# SCH_E-nose-Design_2025-10-13.net
KiCad netlist of a schematic drawn in EasyEDA
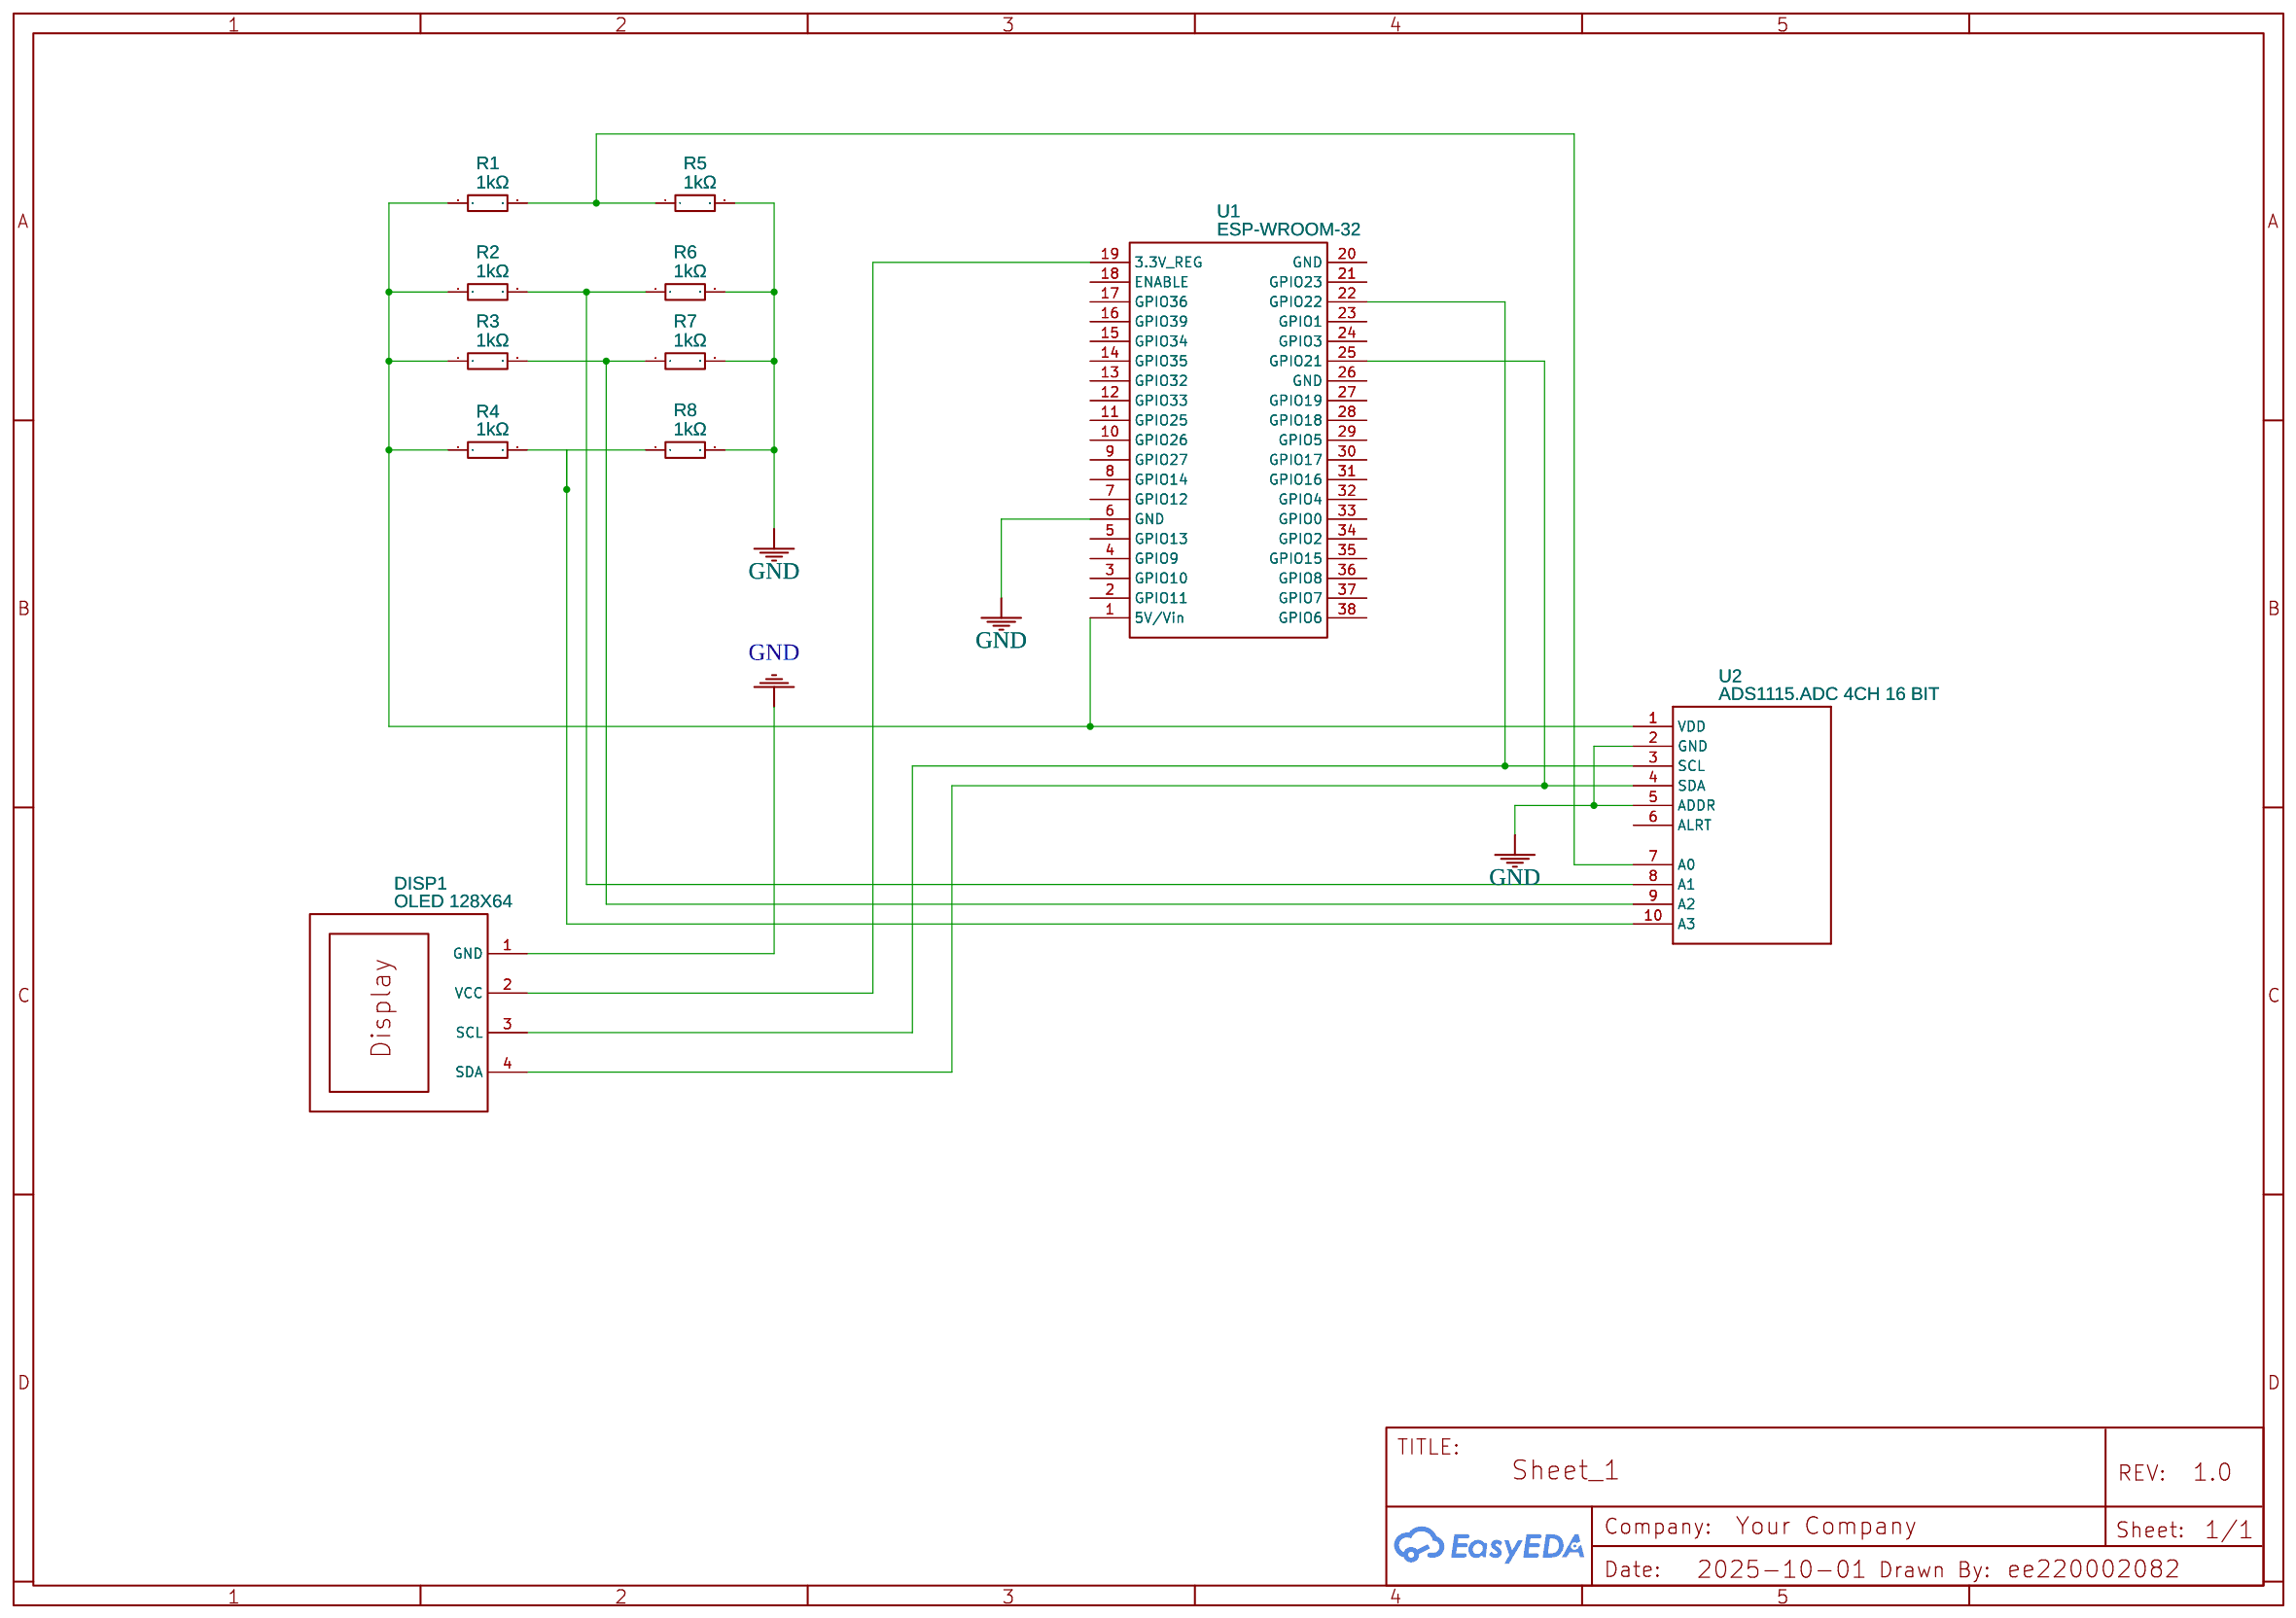
[diagram p0: schematic sheet]

(export (version "E")
  (design (tool "Eeschema 10.0.6"))
  (components
    (comp (ref "DISP1") (value "OLED 128X64") (libsource (lib "") (part "OLED 128X64")))
    (comp (ref "R1")
      (value "1kΩ")
      (fields (field (name "Manufacturer Part") "RC1206JR-071KL") (field (name "Manufacturer") "YAGEO(国巨)"))
      (libsource (lib "") (part "RC1206JR-071KL"))
    )
    (comp (ref "R2")
      (value "1kΩ")
      (fields (field (name "Manufacturer Part") "RC1206JR-071KL") (field (name "Manufacturer") "YAGEO(国巨)"))
      (libsource (lib "") (part "RC1206JR-071KL"))
    )
    (comp (ref "R3")
      (value "1kΩ")
      (fields (field (name "Manufacturer Part") "RC1206JR-071KL") (field (name "Manufacturer") "YAGEO(国巨)"))
      (libsource (lib "") (part "RC1206JR-071KL"))
    )
    (comp (ref "R4")
      (value "1kΩ")
      (fields (field (name "Manufacturer Part") "RC1206JR-071KL") (field (name "Manufacturer") "YAGEO(国巨)"))
      (libsource (lib "") (part "RC1206JR-071KL"))
    )
    (comp (ref "R5")
      (value "1kΩ")
      (fields (field (name "Manufacturer Part") "RC1206JR-071KL") (field (name "Manufacturer") "YAGEO(国巨)"))
      (libsource (lib "") (part "RC1206JR-071KL"))
    )
    (comp (ref "R6")
      (value "1kΩ")
      (fields (field (name "Manufacturer Part") "RC1206JR-071KL") (field (name "Manufacturer") "YAGEO(国巨)"))
      (libsource (lib "") (part "RC1206JR-071KL"))
    )
    (comp (ref "R7")
      (value "1kΩ")
      (fields (field (name "Manufacturer Part") "RC1206JR-071KL") (field (name "Manufacturer") "YAGEO(国巨)"))
      (libsource (lib "") (part "RC1206JR-071KL"))
    )
    (comp (ref "R8")
      (value "1kΩ")
      (fields (field (name "Manufacturer Part") "RC1206JR-071KL") (field (name "Manufacturer") "YAGEO(国巨)"))
      (libsource (lib "") (part "RC1206JR-071KL"))
    )
    (comp (ref "U1") (value "ESP-WROOM-32") (libsource (lib "") (part "ESP-WROOM-32")))
    (comp (ref "U2") (value "ADS1115.ADC 4CH 16 BIT") (libsource (lib "") (part "ADS1115.ADC 4CH 16 BIT")))
  )
  (nets
    (net (code "1") (name "GND") (class "Default")
      (node (ref "DISP1") (pin "1") (pinfunction "GND_1") (pintype "unspecified"))
      (node (ref "R5") (pin "2") (pinfunction "2_2") (pintype "input"))
      (node (ref "R6") (pin "2") (pinfunction "2_2") (pintype "input"))
      (node (ref "R7") (pin "2") (pinfunction "2_2") (pintype "input"))
      (node (ref "R8") (pin "2") (pinfunction "2_2") (pintype "input"))
      (node (ref "U1") (pin "6") (pinfunction "GND_6") (pintype "unspecified"))
      (node (ref "U2") (pin "2") (pinfunction "GND_2") (pintype "passive"))
      (node (ref "U2") (pin "5") (pinfunction "ADDR_5") (pintype "unspecified"))
    )
    (net (code "2") (name "Net-(DISP1-SCL)") (class "Default")
      (node (ref "DISP1") (pin "3") (pinfunction "SCL_3") (pintype "unspecified"))
      (node (ref "U1") (pin "22") (pinfunction "GPIO22_22") (pintype "unspecified"))
      (node (ref "U2") (pin "3") (pinfunction "SCL_3") (pintype "unspecified"))
    )
    (net (code "3") (name "Net-(DISP1-SDA)") (class "Default")
      (node (ref "DISP1") (pin "4") (pinfunction "SDA_4") (pintype "unspecified"))
      (node (ref "U1") (pin "25") (pinfunction "GPIO21_25") (pintype "unspecified"))
      (node (ref "U2") (pin "4") (pinfunction "SDA_4") (pintype "unspecified"))
    )
    (net (code "4") (name "Net-(DISP1-VCC)") (class "Default")
      (node (ref "DISP1") (pin "2") (pinfunction "VCC_2") (pintype "unspecified"))
      (node (ref "U1") (pin "19") (pinfunction "3.3V_REG_19") (pintype "unspecified"))
    )
    (net (code "5") (name "Net-(U1-5V{slash}Vin)") (class "Default")
      (node (ref "R1") (pin "1") (pinfunction "1_1") (pintype "input"))
      (node (ref "R2") (pin "1") (pinfunction "1_1") (pintype "input"))
      (node (ref "R3") (pin "1") (pinfunction "1_1") (pintype "input"))
      (node (ref "R4") (pin "1") (pinfunction "1_1") (pintype "input"))
      (node (ref "U1") (pin "1") (pinfunction "5V/Vin_1") (pintype "unspecified"))
      (node (ref "U2") (pin "1") (pinfunction "VDD_1") (pintype "passive"))
    )
    (net (code "6") (name "Net-(U2-A0)") (class "Default")
      (node (ref "R1") (pin "2") (pinfunction "2_2") (pintype "input"))
      (node (ref "R5") (pin "1") (pinfunction "1_1") (pintype "input"))
      (node (ref "U2") (pin "7") (pinfunction "A0_7") (pintype "input"))
    )
    (net (code "7") (name "Net-(U2-A1)") (class "Default")
      (node (ref "R2") (pin "2") (pinfunction "2_2") (pintype "input"))
      (node (ref "R6") (pin "1") (pinfunction "1_1") (pintype "input"))
      (node (ref "U2") (pin "8") (pinfunction "A1_8") (pintype "input"))
    )
    (net (code "8") (name "Net-(U2-A2)") (class "Default")
      (node (ref "R3") (pin "2") (pinfunction "2_2") (pintype "input"))
      (node (ref "R7") (pin "1") (pinfunction "1_1") (pintype "input"))
      (node (ref "U2") (pin "9") (pinfunction "A2_9") (pintype "input"))
    )
    (net (code "9") (name "Net-(U2-A3)") (class "Default")
      (node (ref "R4") (pin "2") (pinfunction "2_2") (pintype "input"))
      (node (ref "R8") (pin "1") (pinfunction "1_1") (pintype "input"))
      (node (ref "U2") (pin "10") (pinfunction "A3_10") (pintype "input"))
    )
    (net (code "10") (name "unconnected-(U1-ENABLE-Pad18)") (class "Default")
      (node (ref "U1") (pin "18") (pinfunction "ENABLE_18") (pintype "unspecified"))
    )
    (net (code "11") (name "unconnected-(U1-GND-Pad20)") (class "Default")
      (node (ref "U1") (pin "20") (pinfunction "GND_20") (pintype "unspecified"))
    )
    (net (code "12") (name "unconnected-(U1-GND-Pad26)") (class "Default")
      (node (ref "U1") (pin "26") (pinfunction "GND_26") (pintype "unspecified"))
    )
    (net (code "13") (name "unconnected-(U1-GPIO0-Pad33)") (class "Default")
      (node (ref "U1") (pin "33") (pinfunction "GPIO0_33") (pintype "unspecified"))
    )
    (net (code "14") (name "unconnected-(U1-GPIO1-Pad23)") (class "Default")
      (node (ref "U1") (pin "23") (pinfunction "GPIO1_23") (pintype "unspecified"))
    )
    (net (code "15") (name "unconnected-(U1-GPIO2-Pad34)") (class "Default")
      (node (ref "U1") (pin "34") (pinfunction "GPIO2_34") (pintype "unspecified"))
    )
    (net (code "16") (name "unconnected-(U1-GPIO3-Pad24)") (class "Default")
      (node (ref "U1") (pin "24") (pinfunction "GPIO3_24") (pintype "unspecified"))
    )
    (net (code "17") (name "unconnected-(U1-GPIO4-Pad32)") (class "Default")
      (node (ref "U1") (pin "32") (pinfunction "GPIO4_32") (pintype "unspecified"))
    )
    (net (code "18") (name "unconnected-(U1-GPIO5-Pad29)") (class "Default")
      (node (ref "U1") (pin "29") (pinfunction "GPIO5_29") (pintype "unspecified"))
    )
    (net (code "19") (name "unconnected-(U1-GPIO6-Pad38)") (class "Default")
      (node (ref "U1") (pin "38") (pinfunction "GPIO6_38") (pintype "unspecified"))
    )
    (net (code "20") (name "unconnected-(U1-GPIO7-Pad37)") (class "Default")
      (node (ref "U1") (pin "37") (pinfunction "GPIO7_37") (pintype "unspecified"))
    )
    (net (code "21") (name "unconnected-(U1-GPIO8-Pad36)") (class "Default")
      (node (ref "U1") (pin "36") (pinfunction "GPIO8_36") (pintype "unspecified"))
    )
    (net (code "22") (name "unconnected-(U1-GPIO9-Pad4)") (class "Default")
      (node (ref "U1") (pin "4") (pinfunction "GPIO9_4") (pintype "unspecified"))
    )
    (net (code "23") (name "unconnected-(U1-GPIO10-Pad3)") (class "Default")
      (node (ref "U1") (pin "3") (pinfunction "GPIO10_3") (pintype "unspecified"))
    )
    (net (code "24") (name "unconnected-(U1-GPIO11-Pad2)") (class "Default")
      (node (ref "U1") (pin "2") (pinfunction "GPIO11_2") (pintype "unspecified"))
    )
    (net (code "25") (name "unconnected-(U1-GPIO12-Pad7)") (class "Default")
      (node (ref "U1") (pin "7") (pinfunction "GPIO12_7") (pintype "unspecified"))
    )
    (net (code "26") (name "unconnected-(U1-GPIO13-Pad5)") (class "Default")
      (node (ref "U1") (pin "5") (pinfunction "GPIO13_5") (pintype "unspecified"))
    )
    (net (code "27") (name "unconnected-(U1-GPIO14-Pad8)") (class "Default")
      (node (ref "U1") (pin "8") (pinfunction "GPIO14_8") (pintype "unspecified"))
    )
    (net (code "28") (name "unconnected-(U1-GPIO15-Pad35)") (class "Default")
      (node (ref "U1") (pin "35") (pinfunction "GPIO15_35") (pintype "unspecified"))
    )
    (net (code "29") (name "unconnected-(U1-GPIO16-Pad31)") (class "Default")
      (node (ref "U1") (pin "31") (pinfunction "GPIO16_31") (pintype "unspecified"))
    )
    (net (code "30") (name "unconnected-(U1-GPIO17-Pad30)") (class "Default")
      (node (ref "U1") (pin "30") (pinfunction "GPIO17_30") (pintype "unspecified"))
    )
    (net (code "31") (name "unconnected-(U1-GPIO18-Pad28)") (class "Default")
      (node (ref "U1") (pin "28") (pinfunction "GPIO18_28") (pintype "unspecified"))
    )
    (net (code "32") (name "unconnected-(U1-GPIO19-Pad27)") (class "Default")
      (node (ref "U1") (pin "27") (pinfunction "GPIO19_27") (pintype "unspecified"))
    )
    (net (code "33") (name "unconnected-(U1-GPIO23-Pad21)") (class "Default")
      (node (ref "U1") (pin "21") (pinfunction "GPIO23_21") (pintype "unspecified"))
    )
    (net (code "34") (name "unconnected-(U1-GPIO25-Pad11)") (class "Default")
      (node (ref "U1") (pin "11") (pinfunction "GPIO25_11") (pintype "unspecified"))
    )
    (net (code "35") (name "unconnected-(U1-GPIO26-Pad10)") (class "Default")
      (node (ref "U1") (pin "10") (pinfunction "GPIO26_10") (pintype "unspecified"))
    )
    (net (code "36") (name "unconnected-(U1-GPIO27-Pad9)") (class "Default")
      (node (ref "U1") (pin "9") (pinfunction "GPIO27_9") (pintype "unspecified"))
    )
    (net (code "37") (name "unconnected-(U1-GPIO32-Pad13)") (class "Default")
      (node (ref "U1") (pin "13") (pinfunction "GPIO32_13") (pintype "unspecified"))
    )
    (net (code "38") (name "unconnected-(U1-GPIO33-Pad12)") (class "Default")
      (node (ref "U1") (pin "12") (pinfunction "GPIO33_12") (pintype "unspecified"))
    )
    (net (code "39") (name "unconnected-(U1-GPIO34-Pad15)") (class "Default")
      (node (ref "U1") (pin "15") (pinfunction "GPIO34_15") (pintype "unspecified"))
    )
    (net (code "40") (name "unconnected-(U1-GPIO35-Pad14)") (class "Default")
      (node (ref "U1") (pin "14") (pinfunction "GPIO35_14") (pintype "unspecified"))
    )
    (net (code "41") (name "unconnected-(U1-GPIO36-Pad17)") (class "Default")
      (node (ref "U1") (pin "17") (pinfunction "GPIO36_17") (pintype "unspecified"))
    )
    (net (code "42") (name "unconnected-(U1-GPIO39-Pad16)") (class "Default")
      (node (ref "U1") (pin "16") (pinfunction "GPIO39_16") (pintype "unspecified"))
    )
    (net (code "43") (name "unconnected-(U2-ALRT-Pad6)") (class "Default")
      (node (ref "U2") (pin "6") (pinfunction "ALRT_6") (pintype "unspecified"))
    )
  )
)
